# RelayCTRL.net
KiCad netlist of a schematic drawn in EAGLE
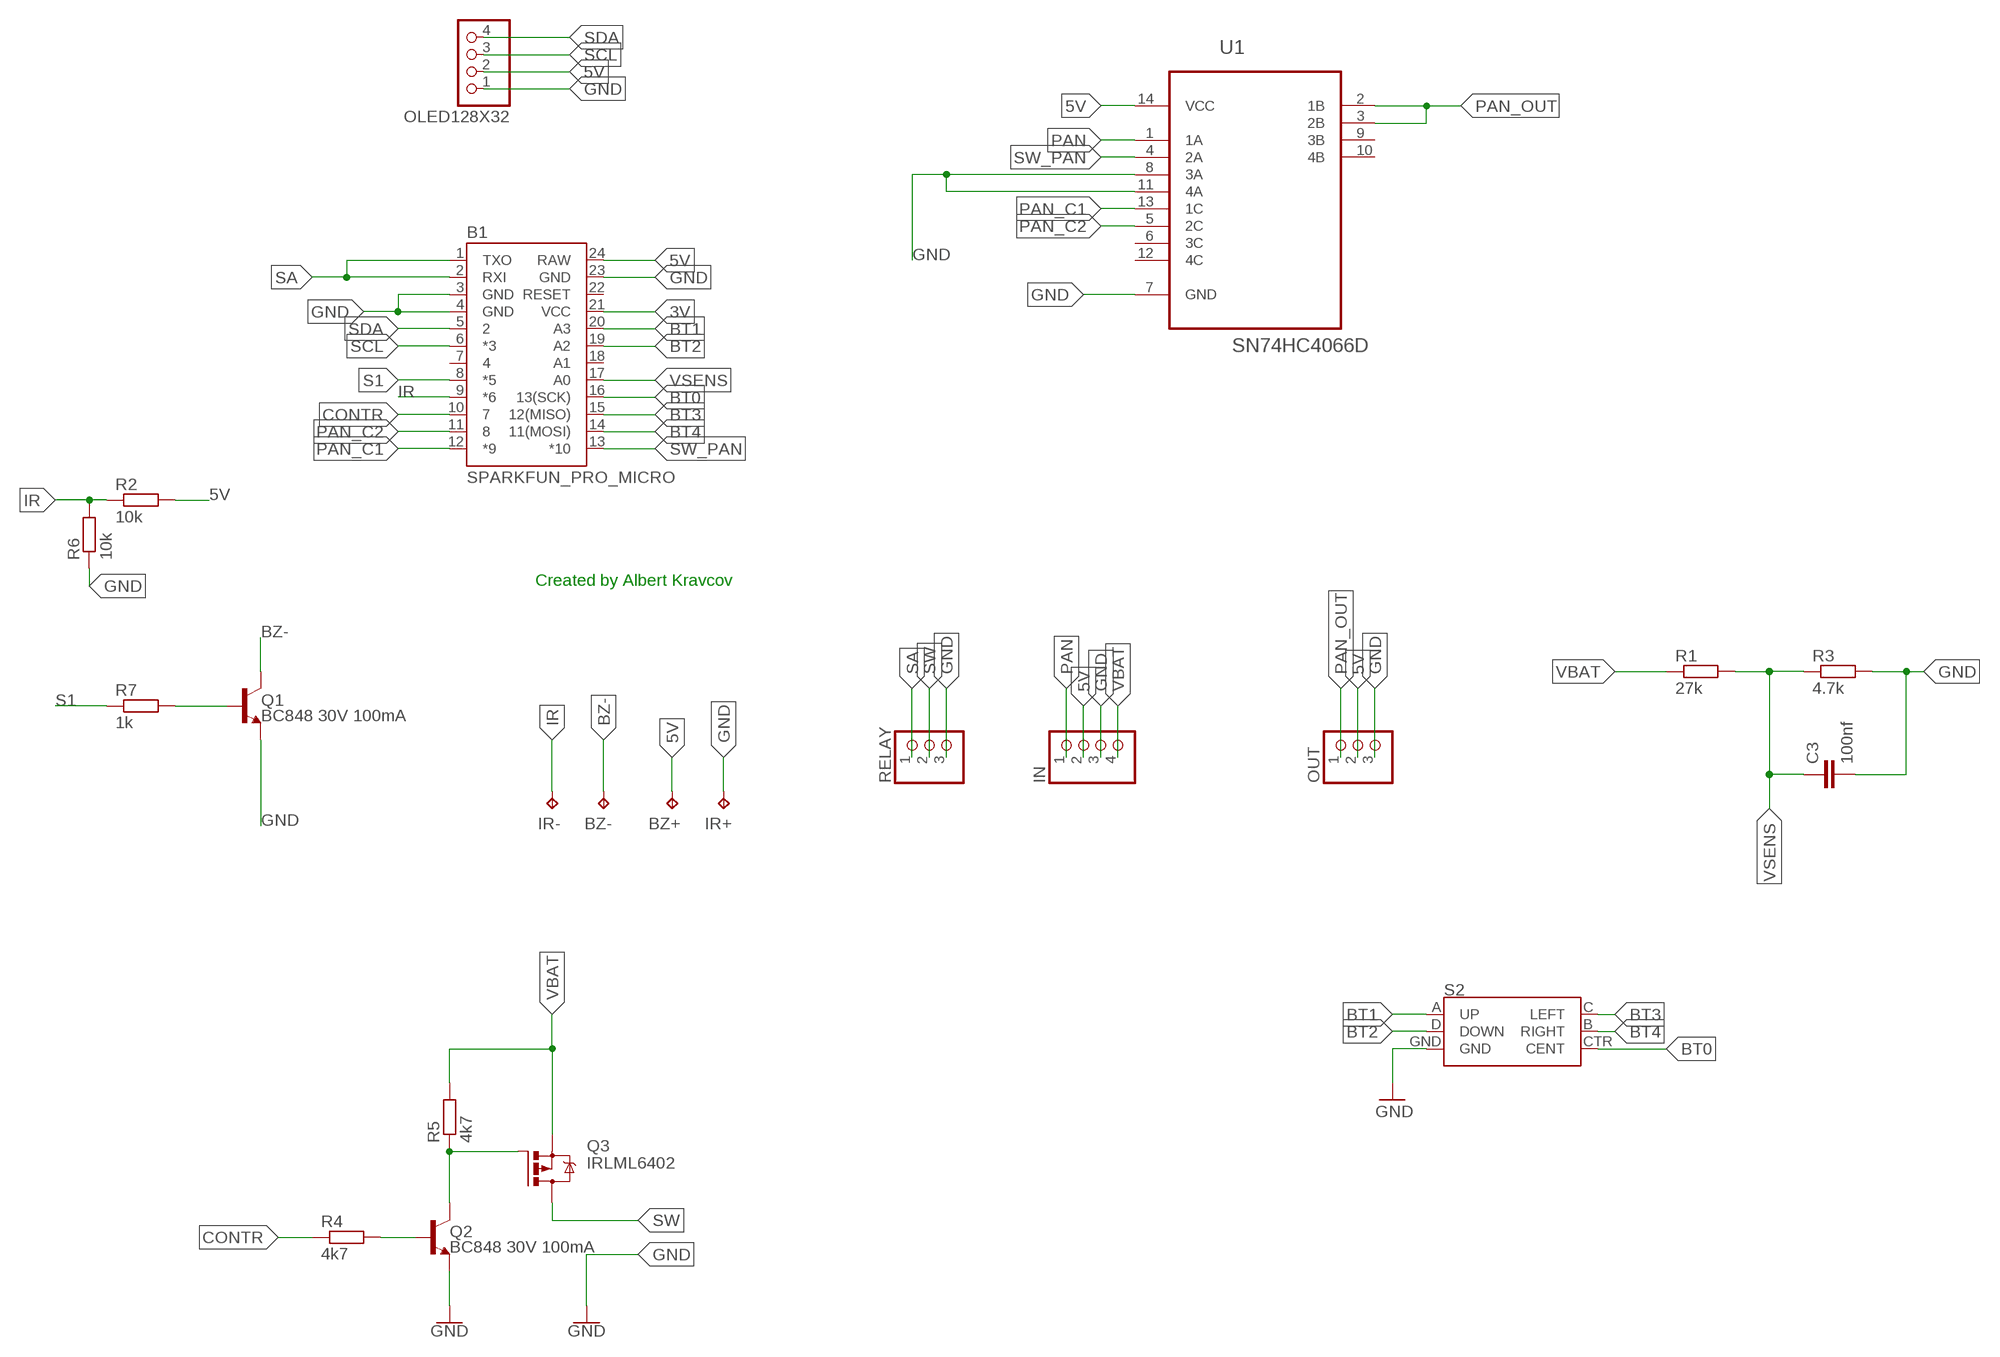
[diagram p0: schematic, sheet 1]

(export (version "E")
  (design (tool "Eeschema 10.0.6"))
  (components
    (comp (ref "B1")
      (value "SPARKFUN_PRO_MICRO")
      (footprint "eagle-import:SPARKFUN_PRO_MICRO")
      (libsource (lib "eagle-import") (part "SPARKFUN_PRO_MICRO"))
    )
    (comp (ref "BZ+")
      (value "TPTP15R")
      (footprint "eagle-import:TP15R")
      (libsource (lib "eagle-import") (part "TPTP15R"))
    )
    (comp (ref "BZ-")
      (value "TPTP15R")
      (footprint "eagle-import:TP15R")
      (libsource (lib "eagle-import") (part "TPTP15R"))
    )
    (comp (ref "C3")
      (value "100nf")
      (footprint "eagle-import:C1206")
      (libsource (lib "eagle-import") (part "C-EUC1206"))
    )
    (comp (ref "IN")
      (value "PINHD-1X4")
      (footprint "eagle-import:1X04")
      (libsource (lib "eagle-import") (part "PINHD-1X4"))
    )
    (comp (ref "IR+")
      (value "TPTP15R")
      (footprint "eagle-import:TP15R")
      (libsource (lib "eagle-import") (part "TPTP15R"))
    )
    (comp (ref "IR-")
      (value "TPTP15R")
      (footprint "eagle-import:TP15R")
      (libsource (lib "eagle-import") (part "TPTP15R"))
    )
    (comp (ref "OLED128X32")
      (value "PINHD-1X4")
      (footprint "eagle-import:1X04")
      (libsource (lib "eagle-import") (part "PINHD-1X4"))
    )
    (comp (ref "OUT")
      (value "PINHD-1X3")
      (footprint "eagle-import:1X03")
      (libsource (lib "eagle-import") (part "PINHD-1X3"))
    )
    (comp (ref "Q1")
      (value "BC848 30V 100mA")
      (footprint "eagle-import:SOT23-3")
      (libsource (lib "eagle-import") (part "TRANS_NPN-MMBT2222AL"))
    )
    (comp (ref "Q2")
      (value "BC848 30V 100mA")
      (footprint "eagle-import:SOT23-3")
      (libsource (lib "eagle-import") (part "TRANS_NPN-MMBT2222AL"))
    )
    (comp (ref "Q3")
      (value "IRLML6402")
      (footprint "eagle-import:MICRO3")
      (libsource (lib "eagle-import") (part "IRLML5203"))
    )
    (comp (ref "R1")
      (value "27k")
      (footprint "eagle-import:R1206")
      (libsource (lib "eagle-import") (part "R-EU_R1206"))
    )
    (comp (ref "R2")
      (value "10k")
      (footprint "eagle-import:R0603")
      (libsource (lib "eagle-import") (part "R-EU_R0603"))
    )
    (comp (ref "R3")
      (value "4.7k")
      (footprint "eagle-import:R1206")
      (libsource (lib "eagle-import") (part "R-EU_R1206"))
    )
    (comp (ref "R4")
      (value "4k7")
      (footprint "eagle-import:R0603")
      (libsource (lib "eagle-import") (part "resistor_348_R-EU_R0603"))
    )
    (comp (ref "R5")
      (value "4k7")
      (footprint "eagle-import:R0603")
      (libsource (lib "eagle-import") (part "resistor_348_R-EU_R0603"))
    )
    (comp (ref "R6")
      (value "10k")
      (footprint "eagle-import:R0603")
      (libsource (lib "eagle-import") (part "R-EU_R0603"))
    )
    (comp (ref "R7")
      (value "1k")
      (footprint "eagle-import:R0603")
      (libsource (lib "eagle-import") (part "R-EU_R0603"))
    )
    (comp (ref "RELAY")
      (value "PINHD-1X3")
      (footprint "eagle-import:1X03")
      (libsource (lib "eagle-import") (part "PINHD-1X3"))
    )
    (comp (ref "S2")
      (value "JOYSTICK_MINI")
      (footprint "eagle-import:JOYSTICK_MINI")
      (libsource (lib "eagle-import") (part "JOYSTICK_MINI"))
    )
    (comp (ref "U1")
      (value "SN74HC4066D")
      (footprint "eagle-import:SOIC127P600X175-14N")
      (fields (field (name "MF") "Texas Instruments"))
      (libsource (lib "eagle-import") (part "SN74HC4066D"))
    )
  )
  (nets
    (net (code "1") (name "3V") (class "Default")
      (node (ref "B1") (pin "21") (pinfunction "VCC_21") (pintype "power_in"))
    )
    (net (code "2") (name "5V") (class "Default")
      (node (ref "B1") (pin "24") (pinfunction "RAW_24") (pintype "power_in"))
      (node (ref "BZ+") (pin "TP") (pinfunction "TP_TP") (pintype "input"))
      (node (ref "IN") (pin "2") (pinfunction "2_2") (pintype "passive"))
      (node (ref "OLED128X32") (pin "2") (pinfunction "2_2") (pintype "passive"))
      (node (ref "OUT") (pin "2") (pinfunction "2_2") (pintype "passive"))
      (node (ref "R2") (pin "2") (pinfunction "2_2") (pintype "passive"))
      (node (ref "U1") (pin "14") (pinfunction "VCC_14") (pintype "power_in"))
    )
    (net (code "3") (name "BT0") (class "Default")
      (node (ref "B1") (pin "16") (pinfunction "13(SCK)_16") (pintype "bidirectional"))
      (node (ref "S2") (pin "CTR") (pinfunction "CENT_CTR") (pintype "bidirectional"))
    )
    (net (code "4") (name "BT1") (class "Default")
      (node (ref "B1") (pin "20") (pinfunction "A3_20") (pintype "bidirectional"))
      (node (ref "S2") (pin "A") (pinfunction "UP_A") (pintype "bidirectional"))
    )
    (net (code "5") (name "BT2") (class "Default")
      (node (ref "B1") (pin "19") (pinfunction "A2_19") (pintype "bidirectional"))
      (node (ref "S2") (pin "D") (pinfunction "DOWN_D") (pintype "bidirectional"))
    )
    (net (code "6") (name "BT3") (class "Default")
      (node (ref "B1") (pin "15") (pinfunction "12(MISO)_15") (pintype "bidirectional"))
      (node (ref "S2") (pin "C") (pinfunction "LEFT_C") (pintype "bidirectional"))
    )
    (net (code "7") (name "BT4") (class "Default")
      (node (ref "B1") (pin "14") (pinfunction "11(MOSI)_14") (pintype "bidirectional"))
      (node (ref "S2") (pin "B") (pinfunction "RIGHT_B") (pintype "bidirectional"))
    )
    (net (code "8") (name "BZ-") (class "Default")
      (node (ref "BZ-") (pin "TP") (pinfunction "TP_TP") (pintype "input"))
      (node (ref "Q1") (pin "3") (pinfunction "C_3") (pintype "passive"))
    )
    (net (code "9") (name "CONTR") (class "Default")
      (node (ref "B1") (pin "10") (pinfunction "7_10") (pintype "bidirectional"))
      (node (ref "R4") (pin "1") (pinfunction "1_1") (pintype "passive"))
    )
    (net (code "10") (name "GND") (class "Default")
      (node (ref "B1") (pin "23") (pinfunction "GND_23") (pintype "power_in"))
      (node (ref "B1") (pin "3") (pinfunction "GND_3") (pintype "power_in"))
      (node (ref "B1") (pin "4") (pinfunction "GND_4") (pintype "power_in"))
      (node (ref "C3") (pin "2") (pinfunction "2_2") (pintype "passive"))
      (node (ref "IN") (pin "3") (pinfunction "3_3") (pintype "passive"))
      (node (ref "IR+") (pin "TP") (pinfunction "TP_TP") (pintype "input"))
      (node (ref "OLED128X32") (pin "1") (pinfunction "1_1") (pintype "passive"))
      (node (ref "OUT") (pin "3") (pinfunction "3_3") (pintype "passive"))
      (node (ref "Q1") (pin "2") (pinfunction "E_2") (pintype "passive"))
      (node (ref "Q2") (pin "2") (pinfunction "E_2") (pintype "passive"))
      (node (ref "R3") (pin "2") (pinfunction "2_2") (pintype "passive"))
      (node (ref "R6") (pin "1") (pinfunction "1_1") (pintype "passive"))
      (node (ref "RELAY") (pin "3") (pinfunction "3_3") (pintype "passive"))
      (node (ref "S2") (pin "GND") (pinfunction "GND_GND") (pintype "bidirectional"))
      (node (ref "U1") (pin "11") (pinfunction "4A_11") (pintype "input"))
      (node (ref "U1") (pin "7") (pinfunction "GND_7") (pintype "passive"))
      (node (ref "U1") (pin "8") (pinfunction "3A_8") (pintype "input"))
    )
    (net (code "11") (name "IR") (class "Default")
      (node (ref "B1") (pin "9") (pinfunction "*6_9") (pintype "bidirectional"))
      (node (ref "IR-") (pin "TP") (pinfunction "TP_TP") (pintype "input"))
      (node (ref "R2") (pin "1") (pinfunction "1_1") (pintype "passive"))
      (node (ref "R6") (pin "2") (pinfunction "2_2") (pintype "passive"))
    )
    (net (code "12") (name "Net-(Q1-B)") (class "Default")
      (node (ref "Q1") (pin "1") (pinfunction "B_1") (pintype "passive"))
      (node (ref "R7") (pin "2") (pinfunction "2_2") (pintype "passive"))
    )
    (net (code "13") (name "Net-(Q2-B)") (class "Default")
      (node (ref "Q2") (pin "1") (pinfunction "B_1") (pintype "passive"))
      (node (ref "R4") (pin "2") (pinfunction "2_2") (pintype "passive"))
    )
    (net (code "14") (name "Net-(Q2-C)") (class "Default")
      (node (ref "Q2") (pin "3") (pinfunction "C_3") (pintype "passive"))
      (node (ref "Q3") (pin "1") (pinfunction "G_1") (pintype "passive"))
      (node (ref "R5") (pin "1") (pinfunction "1_1") (pintype "passive"))
    )
    (net (code "15") (name "PAN") (class "Default")
      (node (ref "IN") (pin "1") (pinfunction "1_1") (pintype "passive"))
      (node (ref "U1") (pin "1") (pinfunction "1A_1") (pintype "input"))
    )
    (net (code "16") (name "PAN_C1") (class "Default")
      (node (ref "B1") (pin "12") (pinfunction "*9_12") (pintype "bidirectional"))
      (node (ref "U1") (pin "13") (pinfunction "1C_13") (pintype "input"))
    )
    (net (code "17") (name "PAN_C2") (class "Default")
      (node (ref "B1") (pin "11") (pinfunction "8_11") (pintype "bidirectional"))
      (node (ref "U1") (pin "5") (pinfunction "2C_5") (pintype "input"))
    )
    (net (code "18") (name "PAN_OUT") (class "Default")
      (node (ref "OUT") (pin "1") (pinfunction "1_1") (pintype "passive"))
      (node (ref "U1") (pin "2") (pinfunction "1B_2") (pintype "output"))
      (node (ref "U1") (pin "3") (pinfunction "2B_3") (pintype "output"))
    )
    (net (code "19") (name "S1") (class "Default")
      (node (ref "B1") (pin "8") (pinfunction "*5_8") (pintype "bidirectional"))
      (node (ref "R7") (pin "1") (pinfunction "1_1") (pintype "passive"))
    )
    (net (code "20") (name "SA") (class "Default")
      (node (ref "B1") (pin "1") (pinfunction "TXO_1") (pintype "bidirectional"))
      (node (ref "B1") (pin "2") (pinfunction "RXI_2") (pintype "bidirectional"))
      (node (ref "RELAY") (pin "1") (pinfunction "1_1") (pintype "passive"))
    )
    (net (code "21") (name "SCL") (class "Default")
      (node (ref "B1") (pin "6") (pinfunction "*3_6") (pintype "bidirectional"))
      (node (ref "OLED128X32") (pin "3") (pinfunction "3_3") (pintype "passive"))
    )
    (net (code "22") (name "SDA") (class "Default")
      (node (ref "B1") (pin "5") (pinfunction "2_5") (pintype "bidirectional"))
      (node (ref "OLED128X32") (pin "4") (pinfunction "4_4") (pintype "passive"))
    )
    (net (code "23") (name "SW") (class "Default")
      (node (ref "Q3") (pin "3") (pinfunction "D_3") (pintype "passive"))
      (node (ref "RELAY") (pin "2") (pinfunction "2_2") (pintype "passive"))
    )
    (net (code "24") (name "SW_PAN") (class "Default")
      (node (ref "B1") (pin "13") (pinfunction "*10_13") (pintype "bidirectional"))
      (node (ref "U1") (pin "4") (pinfunction "2A_4") (pintype "input"))
    )
    (net (code "25") (name "VBAT") (class "Default")
      (node (ref "IN") (pin "4") (pinfunction "4_4") (pintype "passive"))
      (node (ref "Q3") (pin "2") (pinfunction "S_2") (pintype "passive"))
      (node (ref "R1") (pin "1") (pinfunction "1_1") (pintype "passive"))
      (node (ref "R5") (pin "2") (pinfunction "2_2") (pintype "passive"))
    )
    (net (code "26") (name "VSENS") (class "Default")
      (node (ref "B1") (pin "17") (pinfunction "A0_17") (pintype "bidirectional"))
      (node (ref "C3") (pin "1") (pinfunction "1_1") (pintype "passive"))
      (node (ref "R1") (pin "2") (pinfunction "2_2") (pintype "passive"))
      (node (ref "R3") (pin "1") (pinfunction "1_1") (pintype "passive"))
    )
    (net (code "27") (name "unconnected-(B1-4-Pad7)") (class "Default")
      (node (ref "B1") (pin "7") (pinfunction "4_7") (pintype "bidirectional"))
    )
    (net (code "28") (name "unconnected-(B1-A1-Pad18)") (class "Default")
      (node (ref "B1") (pin "18") (pinfunction "A1_18") (pintype "bidirectional"))
    )
    (net (code "29") (name "unconnected-(B1-RESET-Pad22)") (class "Default")
      (node (ref "B1") (pin "22") (pinfunction "RESET_22") (pintype "bidirectional"))
    )
    (net (code "30") (name "unconnected-(U1-3B-Pad9)") (class "Default")
      (node (ref "U1") (pin "9") (pinfunction "3B_9") (pintype "output"))
    )
    (net (code "31") (name "unconnected-(U1-3C-Pad6)") (class "Default")
      (node (ref "U1") (pin "6") (pinfunction "3C_6") (pintype "input"))
    )
    (net (code "32") (name "unconnected-(U1-4B-Pad10)") (class "Default")
      (node (ref "U1") (pin "10") (pinfunction "4B_10") (pintype "output"))
    )
    (net (code "33") (name "unconnected-(U1-4C-Pad12)") (class "Default")
      (node (ref "U1") (pin "12") (pinfunction "4C_12") (pintype "input"))
    )
  )
)
